# Sheet1.net
KiCad netlist of a schematic drawn in Altium Designer
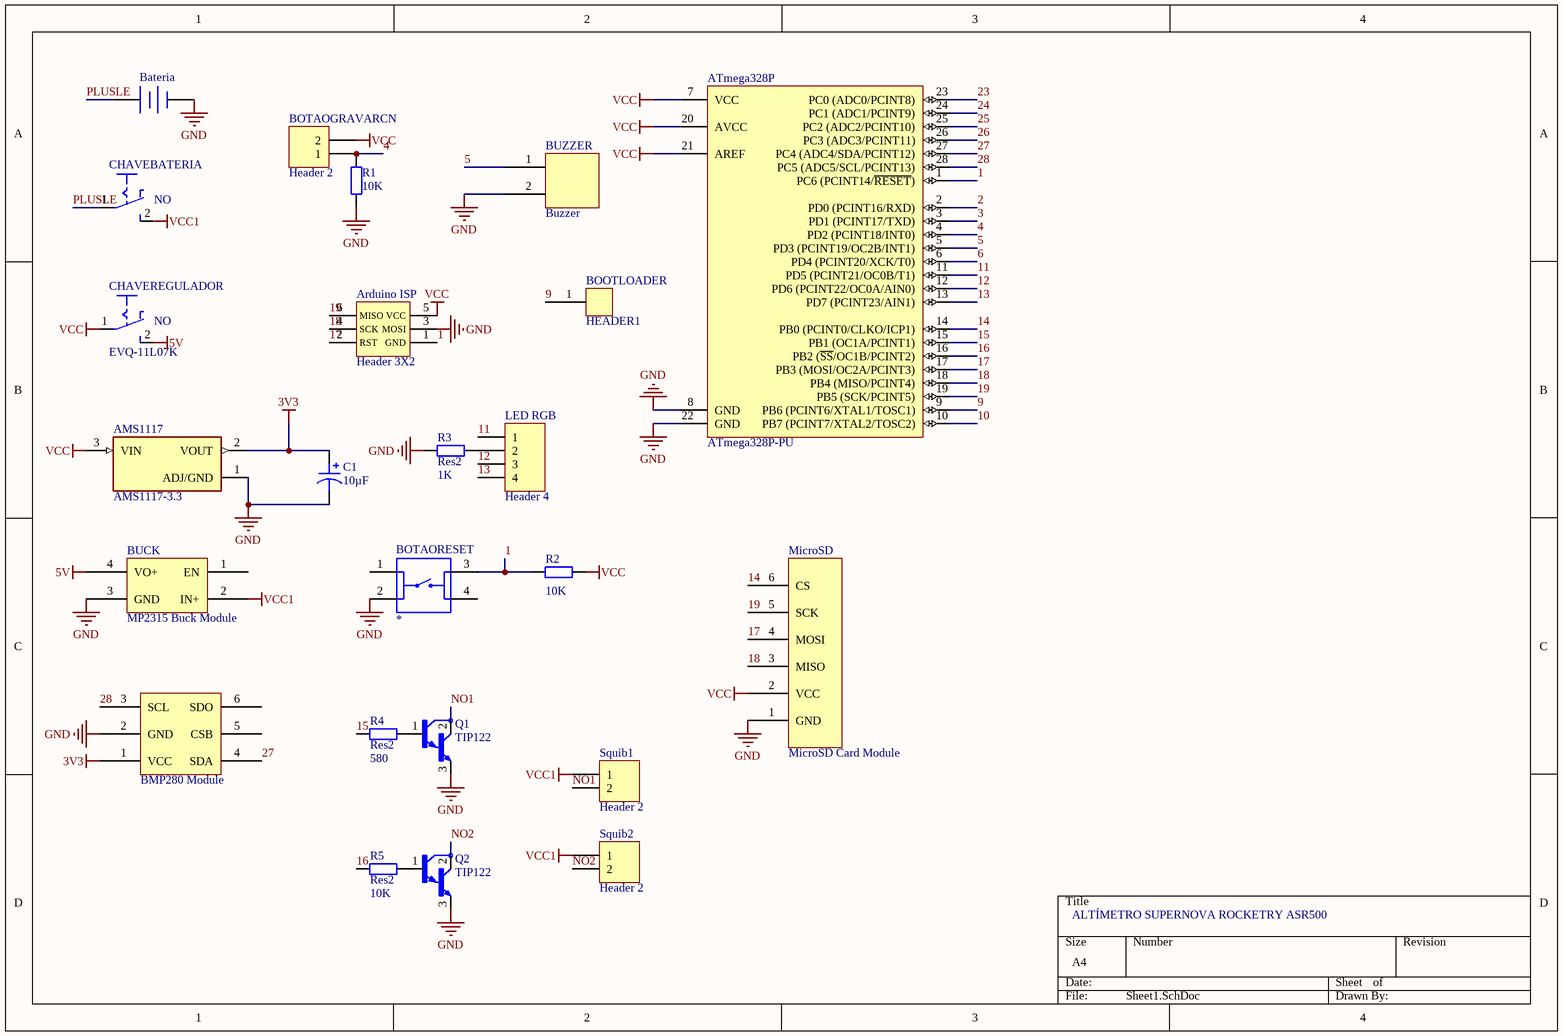
[diagram p0: Sheet1.SchDoc]

(export (version "E")
  (design (tool "Eeschema 10.0.6"))
  (components
    (comp (ref "AMS1117")
      (value "AMS1117-3.3")
      (footprint "SOT229P700X180-4N")
      (description "Sot223/Pkg 1-Amp 3.3-Volt Low Drop Out Voltage Regulatator")
      (fields (field (name "MF") "Advanced Monolithic Systems"))
      (libsource (lib "AMS1117-3.3") (part "AMS1117-3.3"))
    )
    (comp (ref "Arduino ISP")
      (value "Header 3X2")
      (footprint "HDR2X3")
      (description "Header, 3-Pin, Dual row")
      (fields (field (name "PUBLISHER") "Altium Limited"))
      (libsource (lib "Miscellaneous Connectors") (part "Header 3X2"))
    )
    (comp (ref "ATmega328P")
      (value "ATmega328P-PU")
      (footprint "28P3")
      (fields (field (name "PUBLISHER") "Altium Limited"))
      (libsource (lib "Atmel Microcontroller 8-Bit megaAVR") (part "ATmega328P-PU"))
    )
    (comp (ref "Bateria")
      (value "Battery")
      (footprint "BAT-2")
      (description "Multicell Battery")
      (fields (field (name "PUBLISHER") "Altium Limited"))
      (libsource (lib "Miscellaneous Devices") (part "Battery"))
    )
    (comp (ref "BMP280")
      (value "BMP280 Module")
      (footprint "BMP280 Module")
      (description "BMP280 Module REF. 9SS08")
      (libsource (lib "Schlib1") (part "BMP280 Module"))
    )
    (comp (ref "BOOTLOADER")
      (value "HEADER1")
      (footprint "HEADER1")
      (libsource (lib "Schlib1") (part "HEADER1"))
    )
    (comp (ref "BOTAOGRAVARCN")
      (value "Header 2")
      (footprint "HDR1X2")
      (description "Header, 2-Pin")
      (fields (field (name "PUBLISHER") "Altium Limited"))
      (libsource (lib "") (part "Header 2_1"))
    )
    (comp (ref "BOTAORESET")
      (value "1825910-6")
      (footprint "SW_1825910-6-4")
      (description "Switch Push Button OFF _ON_ SPST Round Button 0.05A 24VDC Momentary Contact PC Pins Thru-Hole")
      (fields
        (field (name "MF") "TE Connectivity")
        (field (name "DIGI-KEY_PART_NUMBER") "450-1650-ND")
        (field (name "COMMENT_1") "*")
      )
      (libsource (lib "1825910-6") (part "1825910-6"))
    )
    (comp (ref "BUCK")
      (value "MP2315 Buck Module")
      (footprint "MP2315 Buck Module")
      (libsource (lib "Schlib1") (part "MP2315 Buck Module"))
    )
    (comp (ref "BUZZER") (value "Buzzer") (footprint "BUZZER") (libsource (lib "Schlib1") (part "Buzzer")))
    (comp (ref "C1")
      (value "10µF")
      (footprint "CAP AL TH D8 L3.5 H12.5")
      (description "CAP ALUM 10UF 20% 100V RADIAL")
      (fields (field (name "PART NUMBER") "UKL2A100MPD1TD") (field (name "MANUFACTURER") "Nichicon"))
      (libsource (lib "Celestial Altium Library - altium_library") (part "Polarised Capacitor"))
    )
    (comp (ref "CHAVEBATERIA")
      (value "EVQ-11L07K")
      (footprint "EVQ11")
      (description "Tactile Switch SPST-NO Top Actuated Through Hole")
      (fields (field (name "MF") "Panasonic"))
      (libsource (lib "EVQ-11L07K") (part "EVQ-11L07K"))
    )
    (comp (ref "CHAVEREGULADOR")
      (value "EVQ-11L07K")
      (footprint "EVQ11")
      (description "Tactile Switch SPST-NO Top Actuated Through Hole")
      (fields (field (name "MF") "Panasonic"))
      (libsource (lib "EVQ-11L07K") (part "EVQ-11L07K"))
    )
    (comp (ref "LED RGB")
      (value "Header 4")
      (footprint "HDR1X4")
      (description "Header, 4-Pin")
      (fields (field (name "PUBLISHER") "Altium Limited"))
      (libsource (lib "Miscellaneous Connectors") (part "Header 4"))
    )
    (comp (ref "MicroSD")
      (value "MicroSD Card Module")
      (footprint "MicroSD Card Module")
      (description "MicroSD Card Module REF. 4MD36")
      (libsource (lib "Schlib1") (part "MicroSD Card Module"))
    )
    (comp (ref "Q1")
      (value "TIP122")
      (footprint "Miscellaneous Devices:TO-220AB")
      (description "Trans Darlington NPN 100V 5A 2000mW Automotive 3-Pin(3+Tab) TO-220 Bag")
      (fields (field (name "MF") "NTE Electronics, Inc"))
      (libsource (lib "TIP122") (part "TIP122"))
    )
    (comp (ref "Q2")
      (value "TIP122")
      (footprint "TO-220AB")
      (description "Trans Darlington NPN 100V 5A 2000mW Automotive 3-Pin(3+Tab) TO-220 Bag")
      (fields (field (name "MF") "NTE Electronics, Inc"))
      (libsource (lib "TIP122") (part "TIP122"))
    )
    (comp (ref "R1")
      (value "10K")
      (footprint "AXIAL-0.4")
      (description "Resistor")
      (fields (field (name "Comment") "Res2") (field (name "PUBLISHER") "Altium Limited"))
      (libsource (lib "Miscellaneous Devices") (part "Res2"))
    )
    (comp (ref "R2")
      (value "10K")
      (footprint "AXIAL-0.4")
      (description "Resistor")
      (fields (field (name "Comment") "Res2") (field (name "PUBLISHER") "Altium Limited"))
      (libsource (lib "") (part "Res2_1"))
    )
    (comp (ref "R3")
      (value "Res2")
      (footprint "AXIAL-0.4")
      (description "Resistor")
      (fields (field (name "ALTIUM_VALUE") "1K") (field (name "PUBLISHER") "Altium Limited"))
      (libsource (lib "") (part "Res2_1"))
    )
    (comp (ref "R4")
      (value "Res2")
      (footprint "AXIAL-0.4")
      (description "Resistor")
      (fields (field (name "ALTIUM_VALUE") "580") (field (name "PUBLISHER") "Altium Limited"))
      (libsource (lib "") (part "Res2_1"))
    )
    (comp (ref "R5")
      (value "Res2")
      (footprint "AXIAL-0.4")
      (description "Resistor")
      (fields (field (name "ALTIUM_VALUE") "10K") (field (name "PUBLISHER") "Altium Limited"))
      (libsource (lib "") (part "Res2_1"))
    )
    (comp (ref "Squib1")
      (value "Header 2")
      (footprint "HDR1X2")
      (description "Header, 2-Pin")
      (fields (field (name "PUBLISHER") "Altium Limited"))
      (libsource (lib "Miscellaneous Connectors") (part "Header 2"))
    )
    (comp (ref "Squib2")
      (value "Header 2")
      (footprint "HDR1X2")
      (description "Header, 2-Pin")
      (fields (field (name "PUBLISHER") "Altium Limited"))
      (libsource (lib "Miscellaneous Connectors") (part "Header 2"))
    )
  )
  (nets
    (net (code "1") (name "/1") (class "Default")
      (node (ref "ATmega328P") (pin "1") (pinfunction "PC6_(PCINT14/~{RESET})_1") (pintype "bidirectional"))
      (node (ref "Arduino ISP") (pin "1") (pinfunction "GND_1") (pintype "passive"))
      (node (ref "BOTAORESET") (pin "3") (pinfunction "3_3") (pintype "passive"))
      (node (ref "R2") (pin "1") (pinfunction "1_1") (pintype "passive"))
    )
    (net (code "2") (name "/2") (class "Default")
      (node (ref "ATmega328P") (pin "2") (pinfunction "PD0_(PCINT16/RXD)_2") (pintype "bidirectional"))
    )
    (net (code "3") (name "/3") (class "Default")
      (node (ref "ATmega328P") (pin "3") (pinfunction "PD1_(PCINT17/TXD)_3") (pintype "bidirectional"))
    )
    (net (code "4") (name "/4") (class "Default")
      (node (ref "ATmega328P") (pin "4") (pinfunction "PD2_(PCINT18/INT0)_4") (pintype "bidirectional"))
      (node (ref "BOTAOGRAVARCN") (pin "1") (pinfunction "1_1") (pintype "passive"))
      (node (ref "R1") (pin "2") (pinfunction "2_2") (pintype "passive"))
    )
    (net (code "5") (name "/5") (class "Default")
      (node (ref "ATmega328P") (pin "5") (pinfunction "PD3_(PCINT19/OC2B/INT1)_5") (pintype "bidirectional"))
      (node (ref "BUZZER") (pin "1") (pinfunction "1_1") (pintype "passive"))
    )
    (net (code "6") (name "/6") (class "Default")
      (node (ref "ATmega328P") (pin "6") (pinfunction "PD4_(PCINT20/XCK/T0)_6") (pintype "bidirectional"))
    )
    (net (code "7") (name "/9") (class "Default")
      (node (ref "ATmega328P") (pin "9") (pinfunction "PB6_(PCINT6/XTAL1/TOSC1)_9") (pintype "bidirectional"))
      (node (ref "BOOTLOADER") (pin "1") (pintype "passive"))
    )
    (net (code "8") (name "/10") (class "Default")
      (node (ref "ATmega328P") (pin "10") (pinfunction "PB7_(PCINT7/XTAL2/TOSC2)_10") (pintype "bidirectional"))
    )
    (net (code "9") (name "/11") (class "Default")
      (node (ref "ATmega328P") (pin "11") (pinfunction "PD5_(PCINT21/OC0B/T1)_11") (pintype "bidirectional"))
      (node (ref "LED RGB") (pin "1") (pinfunction "1_1") (pintype "passive"))
    )
    (net (code "10") (name "/12") (class "Default")
      (node (ref "ATmega328P") (pin "12") (pinfunction "PD6_(PCINT22/OC0A/AIN0)_12") (pintype "bidirectional"))
      (node (ref "LED RGB") (pin "3") (pinfunction "3_3") (pintype "passive"))
    )
    (net (code "11") (name "/13") (class "Default")
      (node (ref "ATmega328P") (pin "13") (pinfunction "PD7_(PCINT23/AIN1)_13") (pintype "bidirectional"))
      (node (ref "LED RGB") (pin "4") (pinfunction "4_4") (pintype "passive"))
    )
    (net (code "12") (name "/14") (class "Default")
      (node (ref "ATmega328P") (pin "14") (pinfunction "PB0_(PCINT0/CLKO/ICP1)_14") (pintype "bidirectional"))
      (node (ref "MicroSD") (pin "6") (pinfunction "CS_6") (pintype "passive"))
    )
    (net (code "13") (name "/15") (class "Default")
      (node (ref "ATmega328P") (pin "15") (pinfunction "PB1_(OC1A/PCINT1)_15") (pintype "bidirectional"))
      (node (ref "R4") (pin "1") (pinfunction "1_1") (pintype "passive"))
    )
    (net (code "14") (name "/16") (class "Default")
      (node (ref "ATmega328P") (pin "16") (pinfunction "PB2_(~{SS}/OC1B/PCINT2)_16") (pintype "bidirectional"))
      (node (ref "R5") (pin "1") (pinfunction "1_1") (pintype "passive"))
    )
    (net (code "15") (name "/17") (class "Default")
      (node (ref "ATmega328P") (pin "17") (pinfunction "PB3_(MOSI/OC2A/PCINT3)_17") (pintype "bidirectional"))
      (node (ref "Arduino ISP") (pin "2") (pinfunction "RST_2") (pintype "passive"))
      (node (ref "MicroSD") (pin "4") (pinfunction "MOSI_4") (pintype "passive"))
    )
    (net (code "16") (name "/18") (class "Default")
      (node (ref "ATmega328P") (pin "18") (pinfunction "PB4_(MISO/PCINT4)_18") (pintype "bidirectional"))
      (node (ref "Arduino ISP") (pin "4") (pinfunction "SCK_4") (pintype "passive"))
      (node (ref "MicroSD") (pin "3") (pinfunction "MISO_3") (pintype "passive"))
    )
    (net (code "17") (name "/19") (class "Default")
      (node (ref "ATmega328P") (pin "19") (pinfunction "PB5_(SCK/PCINT5)_19") (pintype "bidirectional"))
      (node (ref "Arduino ISP") (pin "6") (pinfunction "MISO_6") (pintype "passive"))
      (node (ref "MicroSD") (pin "5") (pinfunction "SCK_5") (pintype "passive"))
    )
    (net (code "18") (name "/23") (class "Default")
      (node (ref "ATmega328P") (pin "23") (pinfunction "PC0_(ADC0/PCINT8)_23") (pintype "bidirectional"))
    )
    (net (code "19") (name "/24") (class "Default")
      (node (ref "ATmega328P") (pin "24") (pinfunction "PC1_(ADC1/PCINT9)_24") (pintype "bidirectional"))
    )
    (net (code "20") (name "/25") (class "Default")
      (node (ref "ATmega328P") (pin "25") (pinfunction "PC2_(ADC2/PCINT10)_25") (pintype "bidirectional"))
    )
    (net (code "21") (name "/26") (class "Default")
      (node (ref "ATmega328P") (pin "26") (pinfunction "PC3_(ADC3/PCINT11)_26") (pintype "bidirectional"))
    )
    (net (code "22") (name "/27") (class "Default")
      (node (ref "ATmega328P") (pin "27") (pinfunction "PC4_(ADC4/SDA/PCINT12)_27") (pintype "bidirectional"))
      (node (ref "BMP280") (pin "4") (pinfunction "SDA_4") (pintype "passive"))
    )
    (net (code "23") (name "/28") (class "Default")
      (node (ref "ATmega328P") (pin "28") (pinfunction "PC5_(ADC5/SCL/PCINT13)_28") (pintype "bidirectional"))
      (node (ref "BMP280") (pin "3") (pinfunction "SCL_3") (pintype "passive"))
    )
    (net (code "24") (name "/NO1") (class "Default")
      (node (ref "Q1") (pin "2") (pinfunction "C_2") (pintype "passive"))
      (node (ref "Squib1") (pin "2") (pinfunction "2_2") (pintype "passive"))
    )
    (net (code "25") (name "/NO2") (class "Default")
      (node (ref "Q2") (pin "2") (pinfunction "C_2") (pintype "passive"))
      (node (ref "Squib2") (pin "2") (pinfunction "2_2") (pintype "passive"))
    )
    (net (code "26") (name "/PLUSLE") (class "Default")
      (node (ref "Bateria") (pin "1") (pinfunction "+_1") (pintype "passive"))
      (node (ref "CHAVEBATERIA") (pin "1") (pinfunction "P_1") (pintype "passive"))
    )
    (net (code "27") (name "3V3") (class "Default")
      (node (ref "AMS1117") (pin "2") (pinfunction "VOUT_2") (pintype "output"))
      (node (ref "BMP280") (pin "1") (pinfunction "VCC_1") (pintype "passive"))
      (node (ref "C1") (pin "1") (pinfunction "1_1") (pintype "passive"))
    )
    (net (code "28") (name "5V") (class "Default")
      (node (ref "BUCK") (pin "4") (pinfunction "VO+_4") (pintype "passive"))
      (node (ref "CHAVEREGULADOR") (pin "2") (pinfunction "S_2") (pintype "passive"))
    )
    (net (code "29") (name "GND") (class "Default")
      (node (ref "AMS1117") (pin "1") (pinfunction "ADJ/GND_1") (pintype "power_in"))
      (node (ref "ATmega328P") (pin "22") (pinfunction "GND_22") (pintype "power_in"))
      (node (ref "ATmega328P") (pin "8") (pinfunction "GND_8") (pintype "power_in"))
      (node (ref "Arduino ISP") (pin "3") (pinfunction "MOSI_3") (pintype "passive"))
      (node (ref "BMP280") (pin "2") (pinfunction "GND_2") (pintype "passive"))
      (node (ref "BOTAORESET") (pin "2") (pinfunction "2_2") (pintype "passive"))
      (node (ref "BUCK") (pin "3") (pinfunction "GND_3") (pintype "passive"))
      (node (ref "BUZZER") (pin "2") (pintype "passive"))
      (node (ref "Bateria") (pin "2") (pinfunction "-_2") (pintype "passive"))
      (node (ref "C1") (pin "2") (pinfunction "2_2") (pintype "passive"))
      (node (ref "MicroSD") (pin "1") (pinfunction "GND_1") (pintype "passive"))
      (node (ref "Q1") (pin "3") (pinfunction "E_3") (pintype "passive"))
      (node (ref "Q2") (pin "3") (pinfunction "E_3") (pintype "passive"))
      (node (ref "R1") (pin "1") (pinfunction "1_1") (pintype "passive"))
      (node (ref "R3") (pin "1") (pinfunction "1_1") (pintype "passive"))
    )
    (net (code "30") (name "Net-(LED RGB-Pad2)") (class "Default")
      (node (ref "LED RGB") (pin "2") (pinfunction "2_2") (pintype "passive"))
      (node (ref "R3") (pin "2") (pinfunction "2_2") (pintype "passive"))
    )
    (net (code "31") (name "Net-(Q1-B)") (class "Default")
      (node (ref "Q1") (pin "1") (pinfunction "B_1") (pintype "passive"))
      (node (ref "R4") (pin "2") (pinfunction "2_2") (pintype "passive"))
    )
    (net (code "32") (name "Net-(Q2-B)") (class "Default")
      (node (ref "Q2") (pin "1") (pinfunction "B_1") (pintype "passive"))
      (node (ref "R5") (pin "2") (pinfunction "2_2") (pintype "passive"))
    )
    (net (code "33") (name "VCC") (class "Default")
      (node (ref "AMS1117") (pin "3") (pinfunction "VIN_3") (pintype "input"))
      (node (ref "ATmega328P") (pin "20") (pinfunction "AVCC_20") (pintype "power_in"))
      (node (ref "ATmega328P") (pin "21") (pinfunction "AREF_21") (pintype "power_in"))
      (node (ref "ATmega328P") (pin "7") (pinfunction "VCC_7") (pintype "power_in"))
      (node (ref "Arduino ISP") (pin "5") (pinfunction "VCC_5") (pintype "passive"))
      (node (ref "BOTAOGRAVARCN") (pin "2") (pinfunction "2_2") (pintype "passive"))
      (node (ref "CHAVEREGULADOR") (pin "1") (pinfunction "P_1") (pintype "passive"))
      (node (ref "MicroSD") (pin "2") (pinfunction "VCC_2") (pintype "passive"))
      (node (ref "R2") (pin "2") (pinfunction "2_2") (pintype "passive"))
    )
    (net (code "34") (name "VCC1") (class "Default")
      (node (ref "BUCK") (pin "2") (pinfunction "IN+_2") (pintype "passive"))
      (node (ref "CHAVEBATERIA") (pin "2") (pinfunction "S_2") (pintype "passive"))
      (node (ref "Squib1") (pin "1") (pinfunction "1_1") (pintype "passive"))
      (node (ref "Squib2") (pin "1") (pinfunction "1_1") (pintype "passive"))
    )
    (net (code "35") (name "unconnected-(BMP280-CSB-Pad5)") (class "Default")
      (node (ref "BMP280") (pin "5") (pinfunction "CSB_5") (pintype "passive"))
    )
    (net (code "36") (name "unconnected-(BMP280-SDO-Pad6)") (class "Default")
      (node (ref "BMP280") (pin "6") (pinfunction "SDO_6") (pintype "passive"))
    )
    (net (code "37") (name "unconnected-(BOTAORESET-Pad1)") (class "Default")
      (node (ref "BOTAORESET") (pin "1") (pinfunction "1_1") (pintype "passive"))
    )
    (net (code "38") (name "unconnected-(BOTAORESET-Pad4)") (class "Default")
      (node (ref "BOTAORESET") (pin "4") (pinfunction "4_4") (pintype "passive"))
    )
    (net (code "39") (name "unconnected-(BUCK-EN-Pad1)") (class "Default")
      (node (ref "BUCK") (pin "1") (pinfunction "EN_1") (pintype "passive"))
    )
  )
)
